# Interface.net
KiCad netlist of a schematic drawn in Altium Designer
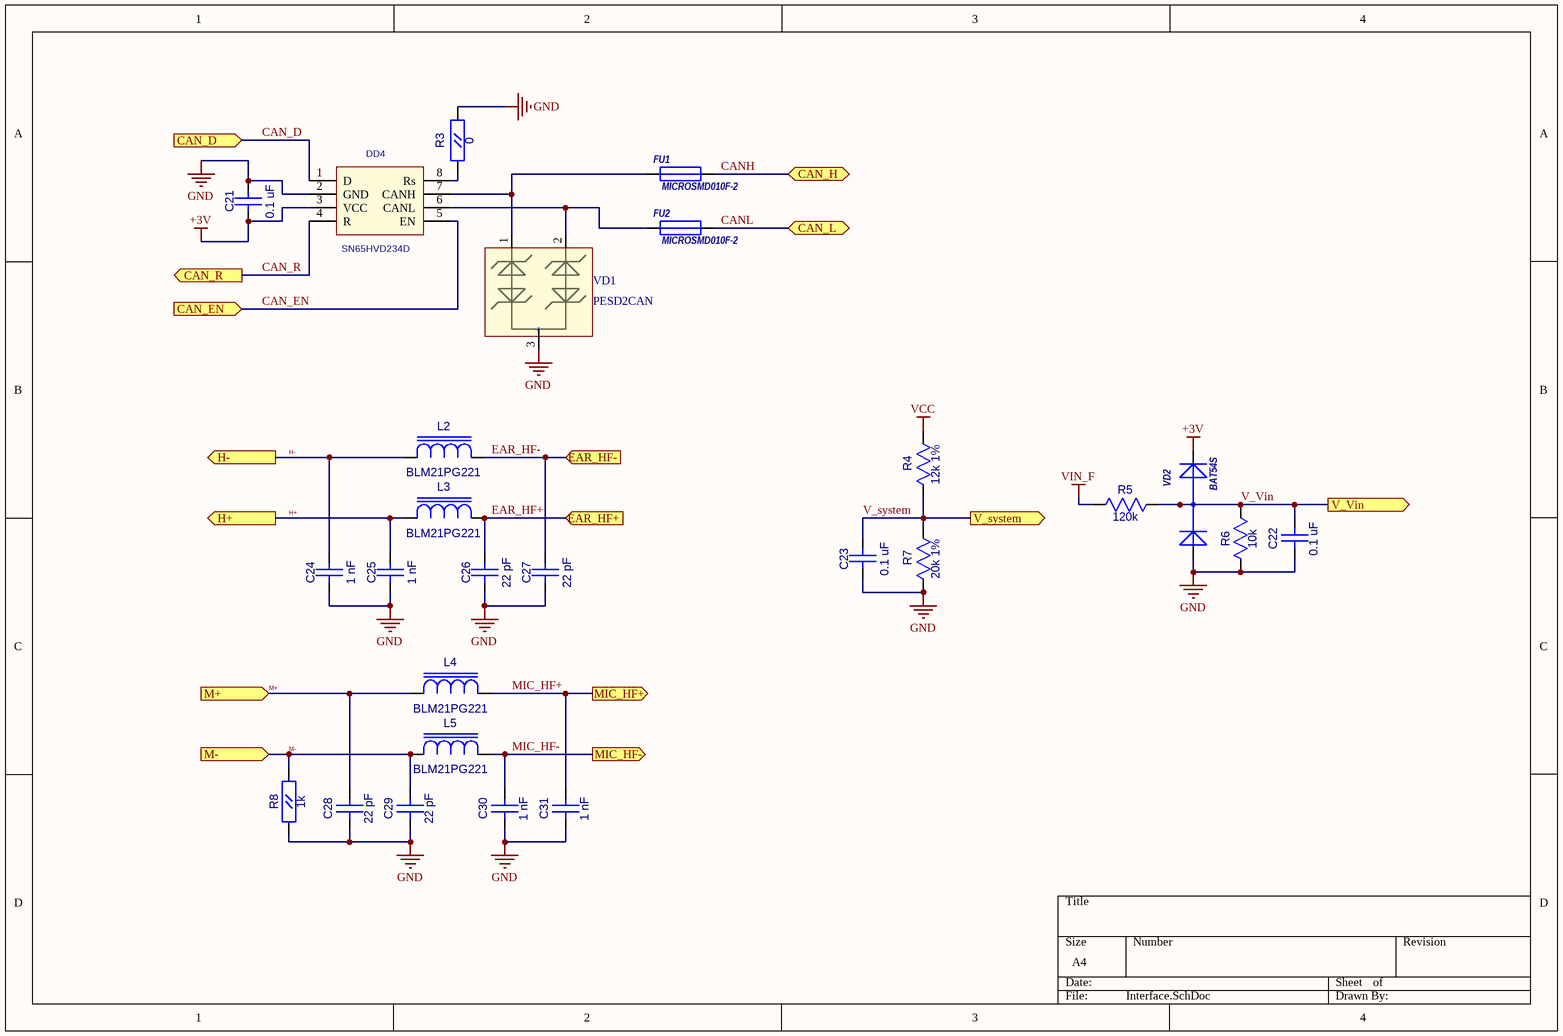
[diagram p0: Interface.SchDoc]

(export (version "E")
  (design (tool "Eeschema 10.0.6"))
  (components
    (comp (ref "C21")
      (value "0.1 uF")
      (footprint "CC0603")
      (description "CC0603")
      (libsource (lib "*") (part "CC0603"))
    )
    (comp (ref "C22")
      (value "0.1 uF")
      (footprint "CC0603-3M")
      (description "CC0603")
      (libsource (lib "gprs_modem") (part "CC0603"))
    )
    (comp (ref "C23")
      (value "0.1 uF")
      (footprint "CC0603-3M")
      (description "CC0603")
      (libsource (lib "gprs_modem") (part "CC0603"))
    )
    (comp (ref "C24")
      (value "1 nF")
      (footprint "CC0603")
      (description "CC0603")
      (libsource (lib "*") (part "CC0603"))
    )
    (comp (ref "C25")
      (value "1 nF")
      (footprint "CC0603")
      (description "CC0603")
      (libsource (lib "*") (part "CC0603"))
    )
    (comp (ref "C26")
      (value "22 pF")
      (footprint "CC0603")
      (description "CC0603")
      (libsource (lib "*") (part "CC0603"))
    )
    (comp (ref "C27")
      (value "22 pF")
      (footprint "CC0603")
      (description "CC0603")
      (libsource (lib "*") (part "CC0603"))
    )
    (comp (ref "C28")
      (value "22 pF")
      (footprint "CC0603")
      (description "CC0603")
      (libsource (lib "*") (part "CC0603"))
    )
    (comp (ref "C29")
      (value "22 pF")
      (footprint "CC0603")
      (description "CC0603")
      (libsource (lib "*") (part "CC0603"))
    )
    (comp (ref "C30")
      (value "1 nF")
      (footprint "CC0603")
      (description "CC0603")
      (libsource (lib "*") (part "CC0603"))
    )
    (comp (ref "C31")
      (value "1 nF")
      (footprint "CC0603")
      (description "CC0603")
      (libsource (lib "*") (part "CC0603"))
    )
    (comp (ref "DD4")
      (value "SN65HVD234D")
      (footprint "SO-8")
      (description "CAN Transceiver")
      (libsource (lib "gprs_modem") (part "SN65HVD234D"))
    )
    (comp (ref "FU1")
      (value "MICROSMD010F-2")
      (footprint "RC1210")
      (description "MICROSMD")
      (libsource (lib "gprs_modem_2") (part "MICROSMD"))
    )
    (comp (ref "FU2")
      (value "MICROSMD010F-2")
      (footprint "RC1210")
      (description "MICROSMD")
      (libsource (lib "gprs_modem_2") (part "MICROSMD"))
    )
    (comp (ref "L2") (value "BLM21PG221") (footprint "RC0805") (libsource (lib "*") (part "BLM21PG221")))
    (comp (ref "L3") (value "BLM21PG221") (footprint "RC0805") (libsource (lib "*") (part "BLM21PG221")))
    (comp (ref "L4") (value "BLM21PG221") (footprint "RC0805") (libsource (lib "") (part "BLM21PG221_1")))
    (comp (ref "L5") (value "BLM21PG221") (footprint "RC0805") (libsource (lib "") (part "BLM21PG221_1")))
    (comp (ref "R3")
      (value "0")
      (footprint "RC0603")
      (description "RC0603")
      (libsource (lib "*") (part "RC0603"))
    )
    (comp (ref "R4")
      (value "12k 1%")
      (footprint "RC0603-3M")
      (description "RC0603")
      (libsource (lib "") (part "RC0603_1"))
    )
    (comp (ref "R5")
      (value "120k")
      (footprint "RC0603-3M")
      (description "RC0603")
      (libsource (lib "") (part "RC0603_1"))
    )
    (comp (ref "R6")
      (value "10k")
      (footprint "RC0603-3M")
      (description "RC0603")
      (libsource (lib "") (part "RC0603_1"))
    )
    (comp (ref "R7")
      (value "20k 1%")
      (footprint "RC0603-3M")
      (description "RC0603")
      (libsource (lib "") (part "RC0603_1"))
    )
    (comp (ref "R8")
      (value "1k")
      (footprint "RC0603")
      (description "RC0603")
      (libsource (lib "*") (part "RC0603"))
    )
    (comp (ref "VD1")
      (value "PESD2CAN")
      (footprint "SOT-23(123)")
      (description "TVS for CAN")
      (libsource (lib "gprs_modem") (part "PESD2CAN"))
    )
    (comp (ref "VD2")
      (value "BAT54S")
      (footprint "SOT-23(GSD)")
      (description "1.0 Ampere General Purpose Rectifier")
      (libsource (lib "gprs_modem") (part "BAT54S"))
    )
  )
  (nets
    (net (code "1") (name "+3V") (class "Default")
      (node (ref "C21") (pin "1") (pinfunction "A_1") (pintype "passive"))
      (node (ref "DD4") (pin "3") (pinfunction "VCC_3") (pintype "passive"))
      (node (ref "VD2") (pin "2") (pinfunction "K_2") (pintype "passive"))
    )
    (net (code "2") (name "/CANH") (class "Default") (node (ref "FU1") (pin "2") (pintype "passive")))
    (net (code "3") (name "/CANL") (class "Default") (node (ref "FU2") (pin "2") (pintype "passive")))
    (net (code "4") (name "/CAN_D") (class "Default")
      (node (ref "DD4") (pin "1") (pinfunction "D_1") (pintype "passive"))
    )
    (net (code "5") (name "/CAN_EN") (class "Default")
      (node (ref "DD4") (pin "5") (pinfunction "EN_5") (pintype "passive"))
    )
    (net (code "6") (name "/CAN_R") (class "Default")
      (node (ref "DD4") (pin "4") (pinfunction "R_4") (pintype "passive"))
    )
    (net (code "7") (name "/EAR_HF+") (class "Default")
      (node (ref "C26") (pin "2") (pinfunction "B_2") (pintype "passive"))
      (node (ref "L3") (pin "1") (pinfunction "A_1") (pintype "passive"))
    )
    (net (code "8") (name "/EAR_HF-") (class "Default")
      (node (ref "C27") (pin "2") (pinfunction "B_2") (pintype "passive"))
      (node (ref "L2") (pin "1") (pinfunction "A_1") (pintype "passive"))
    )
    (net (code "9") (name "/H+") (class "Default")
      (node (ref "C25") (pin "2") (pinfunction "B_2") (pintype "passive"))
      (node (ref "L3") (pin "2") (pinfunction "B_2") (pintype "passive"))
    )
    (net (code "10") (name "/H-") (class "Default")
      (node (ref "C24") (pin "2") (pinfunction "B_2") (pintype "passive"))
      (node (ref "L2") (pin "2") (pinfunction "B_2") (pintype "passive"))
    )
    (net (code "11") (name "/M+") (class "Default")
      (node (ref "C28") (pin "2") (pinfunction "B_2") (pintype "passive"))
      (node (ref "L4") (pin "1") (pinfunction "A_1") (pintype "passive"))
    )
    (net (code "12") (name "/M-") (class "Default")
      (node (ref "C29") (pin "2") (pinfunction "B_2") (pintype "passive"))
      (node (ref "L5") (pin "1") (pinfunction "A_1") (pintype "passive"))
      (node (ref "R8") (pin "2") (pinfunction "B_2") (pintype "passive"))
    )
    (net (code "13") (name "/MIC_HF+") (class "Default")
      (node (ref "C31") (pin "2") (pinfunction "B_2") (pintype "passive"))
      (node (ref "L4") (pin "2") (pinfunction "B_2") (pintype "passive"))
    )
    (net (code "14") (name "/MIC_HF-") (class "Default")
      (node (ref "C30") (pin "2") (pinfunction "B_2") (pintype "passive"))
      (node (ref "L5") (pin "2") (pinfunction "B_2") (pintype "passive"))
    )
    (net (code "15") (name "/V_Vin") (class "Default")
      (node (ref "C22") (pin "1") (pinfunction "A_1") (pintype "passive"))
      (node (ref "R5") (pin "1") (pinfunction "A_1") (pintype "passive"))
      (node (ref "R6") (pin "1") (pinfunction "A_1") (pintype "passive"))
      (node (ref "VD2") (pin "3") (pinfunction "AK_3") (pintype "passive"))
    )
    (net (code "16") (name "/V_system") (class "Default")
      (node (ref "C23") (pin "1") (pinfunction "A_1") (pintype "passive"))
      (node (ref "R4") (pin "1") (pinfunction "A_1") (pintype "passive"))
      (node (ref "R7") (pin "2") (pinfunction "B_2") (pintype "passive"))
    )
    (net (code "17") (name "GND") (class "Default")
      (node (ref "C21") (pin "2") (pinfunction "B_2") (pintype "passive"))
      (node (ref "C22") (pin "2") (pinfunction "B_2") (pintype "passive"))
      (node (ref "C23") (pin "2") (pinfunction "B_2") (pintype "passive"))
      (node (ref "C24") (pin "1") (pinfunction "A_1") (pintype "passive"))
      (node (ref "C25") (pin "1") (pinfunction "A_1") (pintype "passive"))
      (node (ref "C26") (pin "1") (pinfunction "A_1") (pintype "passive"))
      (node (ref "C27") (pin "1") (pinfunction "A_1") (pintype "passive"))
      (node (ref "C28") (pin "1") (pinfunction "A_1") (pintype "passive"))
      (node (ref "C29") (pin "1") (pinfunction "A_1") (pintype "passive"))
      (node (ref "C30") (pin "1") (pinfunction "A_1") (pintype "passive"))
      (node (ref "C31") (pin "1") (pinfunction "A_1") (pintype "passive"))
      (node (ref "DD4") (pin "2") (pinfunction "GND_2") (pintype "passive"))
      (node (ref "R3") (pin "2") (pinfunction "B_2") (pintype "passive"))
      (node (ref "R6") (pin "2") (pinfunction "B_2") (pintype "passive"))
      (node (ref "R7") (pin "1") (pinfunction "A_1") (pintype "passive"))
      (node (ref "R8") (pin "1") (pinfunction "A_1") (pintype "passive"))
      (node (ref "VD1") (pin "3") (pinfunction "3_3") (pintype "passive"))
      (node (ref "VD2") (pin "1") (pinfunction "A_1") (pintype "passive"))
    )
    (net (code "18") (name "Net-(DD4-CANH)") (class "Default")
      (node (ref "DD4") (pin "7") (pinfunction "CANH_7") (pintype "passive"))
      (node (ref "FU1") (pin "1") (pintype "passive"))
      (node (ref "VD1") (pin "1") (pinfunction "1_1") (pintype "passive"))
    )
    (net (code "19") (name "Net-(DD4-CANL)") (class "Default")
      (node (ref "DD4") (pin "6") (pinfunction "CANL_6") (pintype "passive"))
      (node (ref "FU2") (pin "1") (pintype "passive"))
      (node (ref "VD1") (pin "2") (pinfunction "2_2") (pintype "passive"))
    )
    (net (code "20") (name "Net-(DD4-Rs)") (class "Default")
      (node (ref "DD4") (pin "8") (pinfunction "Rs_8") (pintype "passive"))
      (node (ref "R3") (pin "1") (pinfunction "A_1") (pintype "passive"))
    )
    (net (code "21") (name "VCC") (class "Default")
      (node (ref "R4") (pin "2") (pinfunction "B_2") (pintype "passive"))
    )
    (net (code "22") (name "VIN_F") (class "Default")
      (node (ref "R5") (pin "2") (pinfunction "B_2") (pintype "passive"))
    )
  )
)
